# SparkFun_Pi_Wedge_B_Plus_PreAssembled.net
KiCad netlist of a schematic drawn in EAGLE
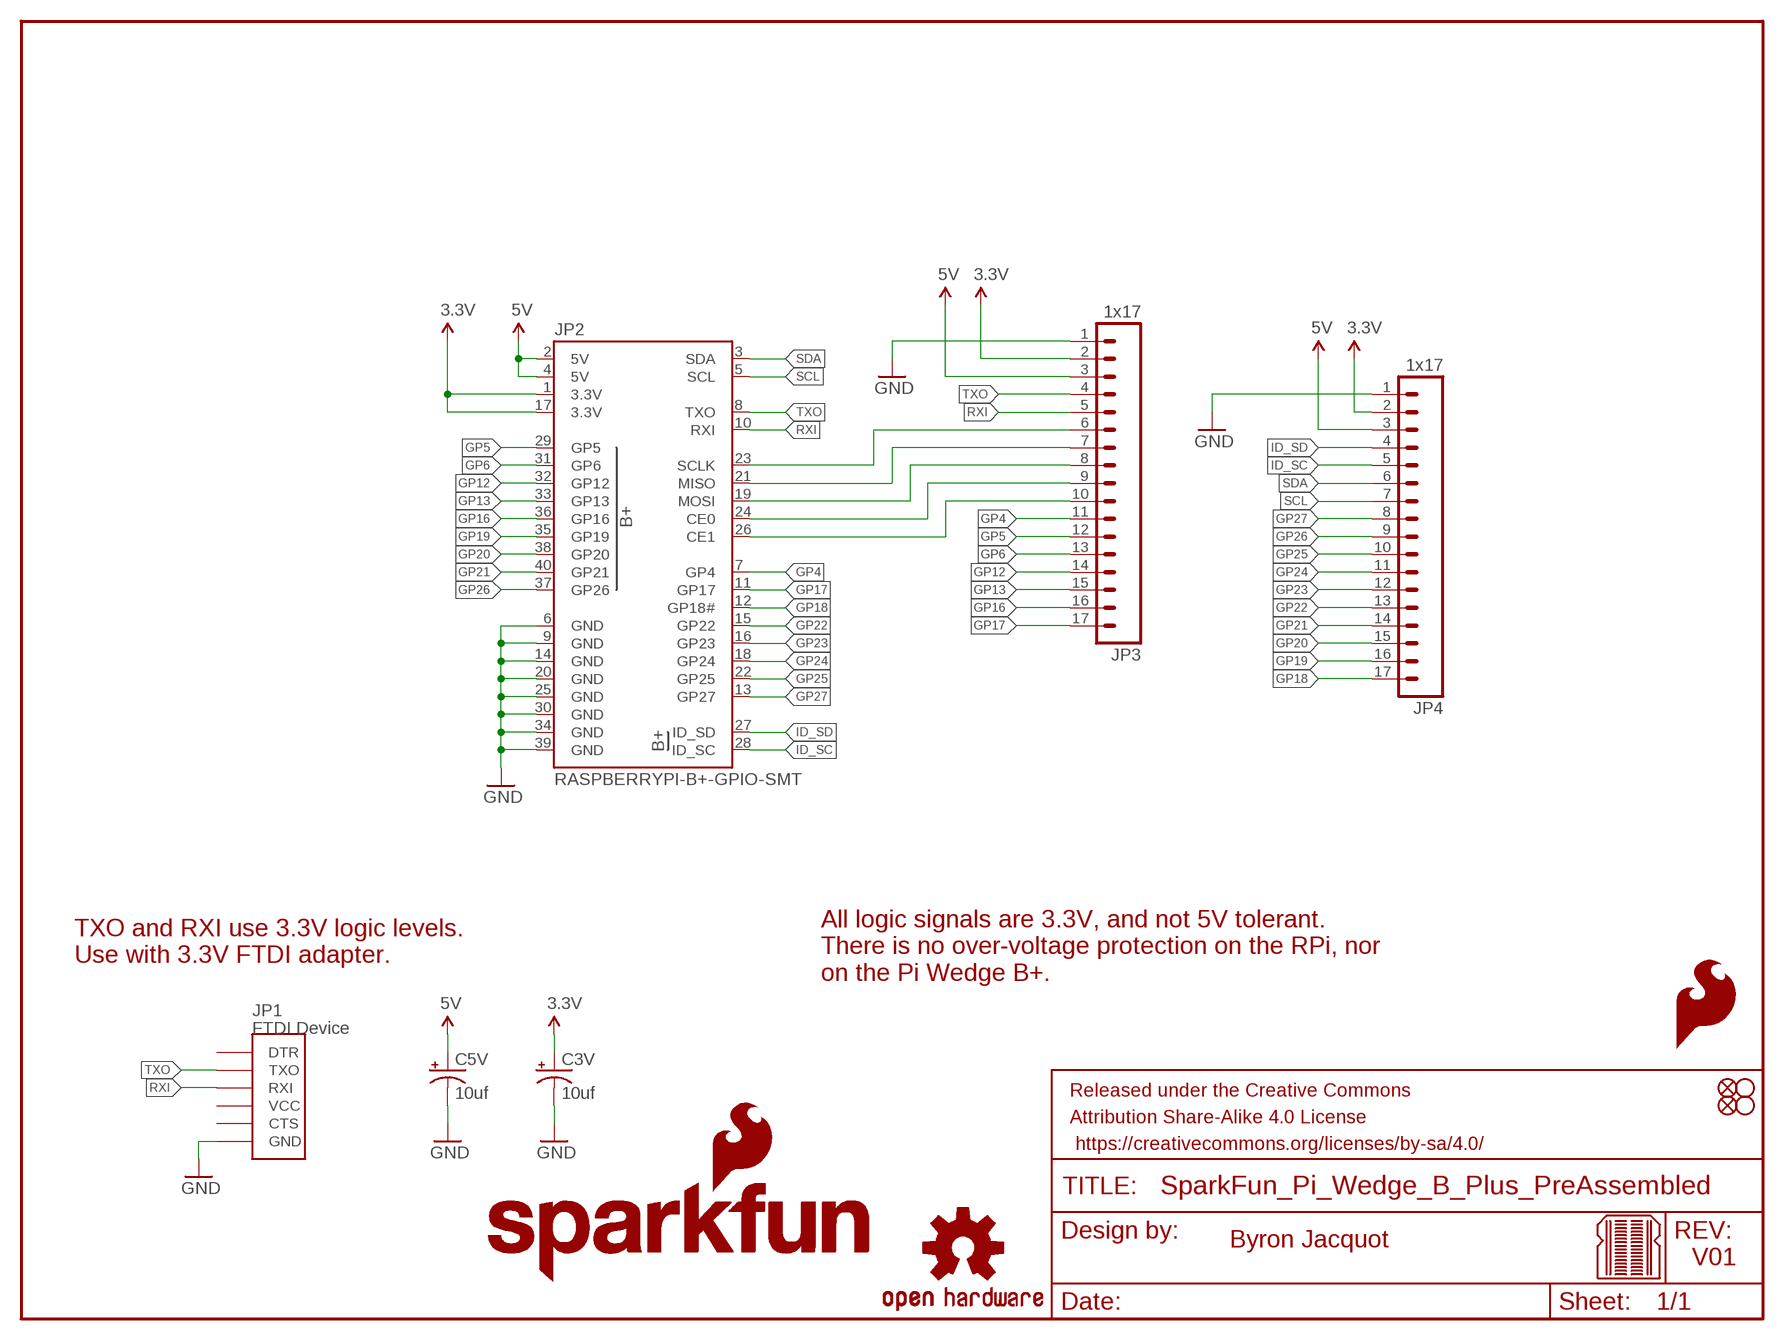
[diagram p0: schematic, sheet 1]

(export (version "E")
  (design (tool "Eeschema 10.0.6"))
  (components
    (comp (ref "C3V")
      (value "10uf")
      (footprint "eagle-import:PANASONIC_D")
      (libsource (lib "eagle-import") (part "47UF-50V-20%(ELECT)"))
    )
    (comp (ref "C5V")
      (value "10uf")
      (footprint "eagle-import:PANASONIC_D")
      (libsource (lib "eagle-import") (part "47UF-50V-20%(ELECT)"))
    )
    (comp (ref "FID1")
      (value "FIDUCIALUFIDUCIAL")
      (footprint "eagle-import:MICRO-FIDUCIAL")
      (libsource (lib "eagle-import") (part "FIDUCIALUFIDUCIAL"))
    )
    (comp (ref "FID2")
      (value "FIDUCIALUFIDUCIAL")
      (footprint "eagle-import:MICRO-FIDUCIAL")
      (libsource (lib "eagle-import") (part "FIDUCIALUFIDUCIAL"))
    )
    (comp (ref "FRAME2")
      (value "FRAME-LETTER")
      (footprint "eagle-import:CREATIVE_COMMONS")
      (libsource (lib "eagle-import") (part "FRAME-LETTER"))
    )
    (comp (ref "JP1")
      (value "FTDI Device")
      (footprint "eagle-import:FTDI_DEVICE_RA_SMT")
      (libsource (lib "eagle-import") (part "FTDI_DEVICERA_SMT"))
    )
    (comp (ref "JP2")
      (value "RASPBERRYPI-B+-GPIO-SMT")
      (footprint "eagle-import:2X20-SHROUDED-SMT")
      (libsource (lib "eagle-import") (part "RASPBERRYPI-B+-GPIO-SMT"))
    )
    (comp (ref "JP3")
      (value "1x17")
      (footprint "eagle-import:1X17_NO_SILK_KIT")
      (libsource (lib "eagle-import") (part "M17KIT"))
    )
    (comp (ref "JP4")
      (value "1x17")
      (footprint "eagle-import:1X17_NO_SILK_KIT")
      (libsource (lib "eagle-import") (part "M17KIT"))
    )
    (comp (ref "LOGO1")
      (value "SFE_LOGO_NAME.2_INCH")
      (footprint "eagle-import:SFE_LOGO_NAME_.2")
      (libsource (lib "eagle-import") (part "SFE_LOGO_NAME.2_INCH"))
    )
    (comp (ref "LOGO2")
      (value "SFE_LOGO_NAME_FLAME.2_INCH")
      (footprint "eagle-import:SFE_LOGO_NAME_FLAME_.2")
      (libsource (lib "eagle-import") (part "SFE_LOGO_NAME_FLAME.2_INCH"))
    )
    (comp (ref "LOGO3")
      (value "SFE_LOGO_FLAME.1_INCH")
      (footprint "eagle-import:SFE_LOGO_FLAME_.1")
      (libsource (lib "eagle-import") (part "SFE_LOGO_FLAME.1_INCH"))
    )
    (comp (ref "LOGO4")
      (value "SFE_LOGO_FLAME.1_INCH")
      (footprint "eagle-import:SFE_LOGO_FLAME_.1")
      (libsource (lib "eagle-import") (part "SFE_LOGO_FLAME.1_INCH"))
    )
    (comp (ref "LOGO5")
      (value "OSHW-LOGOS")
      (footprint "eagle-import:OSHW-LOGO-S")
      (libsource (lib "eagle-import") (part "OSHW-LOGOS"))
    )
    (comp (ref "STANDOFF1")
      (value "STAND-OFF")
      (footprint "eagle-import:STAND-OFF")
      (libsource (lib "eagle-import") (part "STAND-OFF"))
    )
    (comp (ref "STANDOFF2")
      (value "STAND-OFF")
      (footprint "eagle-import:STAND-OFF")
      (libsource (lib "eagle-import") (part "STAND-OFF"))
    )
    (comp (ref "U$2")
      (value "BREADBOARD_PATTERN")
      (footprint "eagle-import:BREADBOARD_SPACING")
      (libsource (lib "eagle-import") (part "BREADBOARD_PATTERN"))
    )
  )
  (nets
    (net (code "1") (name "3.3V") (class "Default")
      (node (ref "C3V") (pin "+") (pinfunction "+_+") (pintype "passive"))
      (node (ref "JP2") (pin "1") (pinfunction "3.3V_1") (pintype "power_in"))
      (node (ref "JP2") (pin "17") (pinfunction "3.3V_17") (pintype "power_in"))
      (node (ref "JP3") (pin "2") (pinfunction "2_2") (pintype "passive"))
      (node (ref "JP4") (pin "2") (pinfunction "2_2") (pintype "passive"))
    )
    (net (code "2") (name "5V") (class "Default")
      (node (ref "C5V") (pin "+") (pinfunction "+_+") (pintype "passive"))
      (node (ref "JP2") (pin "2") (pinfunction "5V_2") (pintype "power_in"))
      (node (ref "JP2") (pin "4") (pinfunction "5V_4") (pintype "power_in"))
      (node (ref "JP3") (pin "3") (pinfunction "3_3") (pintype "passive"))
      (node (ref "JP4") (pin "3") (pinfunction "3_3") (pintype "passive"))
    )
    (net (code "3") (name "GND") (class "Default")
      (node (ref "C3V") (pin "-") (pinfunction "-_-") (pintype "passive"))
      (node (ref "C5V") (pin "-") (pinfunction "-_-") (pintype "passive"))
      (node (ref "JP1") (pin "6") (pinfunction "GND_6") (pintype "bidirectional"))
      (node (ref "JP2") (pin "14") (pinfunction "GND_14") (pintype "power_in"))
      (node (ref "JP2") (pin "20") (pinfunction "GND_20") (pintype "power_in"))
      (node (ref "JP2") (pin "25") (pinfunction "GND_25") (pintype "power_in"))
      (node (ref "JP2") (pin "30") (pinfunction "GND_30") (pintype "power_in"))
      (node (ref "JP2") (pin "34") (pinfunction "GND_34") (pintype "power_in"))
      (node (ref "JP2") (pin "39") (pinfunction "GND_39") (pintype "power_in"))
      (node (ref "JP2") (pin "6") (pinfunction "GND_6") (pintype "power_in"))
      (node (ref "JP2") (pin "9") (pinfunction "GND_9") (pintype "power_in"))
      (node (ref "JP3") (pin "1") (pinfunction "1_1") (pintype "passive"))
      (node (ref "JP4") (pin "1") (pinfunction "1_1") (pintype "passive"))
    )
    (net (code "4") (name "GP4") (class "Default")
      (node (ref "JP2") (pin "7") (pinfunction "GP4_7") (pintype "bidirectional"))
      (node (ref "JP3") (pin "11") (pinfunction "11_11") (pintype "passive"))
    )
    (net (code "5") (name "GP5") (class "Default")
      (node (ref "JP2") (pin "29") (pinfunction "GP5_29") (pintype "bidirectional"))
      (node (ref "JP3") (pin "12") (pinfunction "12_12") (pintype "passive"))
    )
    (net (code "6") (name "GP6") (class "Default")
      (node (ref "JP2") (pin "31") (pinfunction "GP6_31") (pintype "bidirectional"))
      (node (ref "JP3") (pin "13") (pinfunction "13_13") (pintype "passive"))
    )
    (net (code "7") (name "GP12") (class "Default")
      (node (ref "JP2") (pin "32") (pinfunction "GP12_32") (pintype "bidirectional"))
      (node (ref "JP3") (pin "14") (pinfunction "14_14") (pintype "passive"))
    )
    (net (code "8") (name "GP13") (class "Default")
      (node (ref "JP2") (pin "33") (pinfunction "GP13_33") (pintype "bidirectional"))
      (node (ref "JP3") (pin "15") (pinfunction "15_15") (pintype "passive"))
    )
    (net (code "9") (name "GP16") (class "Default")
      (node (ref "JP2") (pin "36") (pinfunction "GP16_36") (pintype "bidirectional"))
      (node (ref "JP3") (pin "16") (pinfunction "16_16") (pintype "passive"))
    )
    (net (code "10") (name "GP17") (class "Default")
      (node (ref "JP2") (pin "11") (pinfunction "GP17_11") (pintype "bidirectional"))
      (node (ref "JP3") (pin "17") (pinfunction "17_17") (pintype "passive"))
    )
    (net (code "11") (name "GP18") (class "Default")
      (node (ref "JP2") (pin "12") (pinfunction "GP18#_12") (pintype "bidirectional"))
      (node (ref "JP4") (pin "17") (pinfunction "17_17") (pintype "passive"))
    )
    (net (code "12") (name "GP19") (class "Default")
      (node (ref "JP2") (pin "35") (pinfunction "GP19_35") (pintype "bidirectional"))
      (node (ref "JP4") (pin "16") (pinfunction "16_16") (pintype "passive"))
    )
    (net (code "13") (name "GP20") (class "Default")
      (node (ref "JP2") (pin "38") (pinfunction "GP20_38") (pintype "bidirectional"))
      (node (ref "JP4") (pin "15") (pinfunction "15_15") (pintype "passive"))
    )
    (net (code "14") (name "GP21") (class "Default")
      (node (ref "JP2") (pin "40") (pinfunction "GP21_40") (pintype "bidirectional"))
      (node (ref "JP4") (pin "14") (pinfunction "14_14") (pintype "passive"))
    )
    (net (code "15") (name "GP22") (class "Default")
      (node (ref "JP2") (pin "15") (pinfunction "GP22_15") (pintype "bidirectional"))
      (node (ref "JP4") (pin "13") (pinfunction "13_13") (pintype "passive"))
    )
    (net (code "16") (name "GP23") (class "Default")
      (node (ref "JP2") (pin "16") (pinfunction "GP23_16") (pintype "bidirectional"))
      (node (ref "JP4") (pin "12") (pinfunction "12_12") (pintype "passive"))
    )
    (net (code "17") (name "GP24") (class "Default")
      (node (ref "JP2") (pin "18") (pinfunction "GP24_18") (pintype "bidirectional"))
      (node (ref "JP4") (pin "11") (pinfunction "11_11") (pintype "passive"))
    )
    (net (code "18") (name "GP25") (class "Default")
      (node (ref "JP2") (pin "22") (pinfunction "GP25_22") (pintype "bidirectional"))
      (node (ref "JP4") (pin "10") (pinfunction "10_10") (pintype "passive"))
    )
    (net (code "19") (name "GP26") (class "Default")
      (node (ref "JP2") (pin "37") (pinfunction "GP26_37") (pintype "bidirectional"))
      (node (ref "JP4") (pin "9") (pinfunction "9_9") (pintype "passive"))
    )
    (net (code "20") (name "GP27") (class "Default")
      (node (ref "JP2") (pin "13") (pinfunction "GP27_13") (pintype "bidirectional"))
      (node (ref "JP4") (pin "8") (pinfunction "8_8") (pintype "passive"))
    )
    (net (code "21") (name "ID_SC") (class "Default")
      (node (ref "JP2") (pin "28") (pinfunction "ID_SC_28") (pintype "bidirectional"))
      (node (ref "JP4") (pin "5") (pinfunction "5_5") (pintype "passive"))
    )
    (net (code "22") (name "ID_SD") (class "Default")
      (node (ref "JP2") (pin "27") (pinfunction "ID_SD_27") (pintype "bidirectional"))
      (node (ref "JP4") (pin "4") (pinfunction "4_4") (pintype "passive"))
    )
    (net (code "23") (name "Net-(JP2-CE0)") (class "Default")
      (node (ref "JP2") (pin "24") (pinfunction "CE0_24") (pintype "output"))
      (node (ref "JP3") (pin "9") (pinfunction "9_9") (pintype "passive"))
    )
    (net (code "24") (name "Net-(JP2-CE1)") (class "Default")
      (node (ref "JP2") (pin "26") (pinfunction "CE1_26") (pintype "output"))
      (node (ref "JP3") (pin "10") (pinfunction "10_10") (pintype "passive"))
    )
    (net (code "25") (name "Net-(JP2-MISO)") (class "Default")
      (node (ref "JP2") (pin "21") (pinfunction "MISO_21") (pintype "input"))
      (node (ref "JP3") (pin "7") (pinfunction "7_7") (pintype "passive"))
    )
    (net (code "26") (name "Net-(JP2-MOSI)") (class "Default")
      (node (ref "JP2") (pin "19") (pinfunction "MOSI_19") (pintype "output"))
      (node (ref "JP3") (pin "8") (pinfunction "8_8") (pintype "passive"))
    )
    (net (code "27") (name "Net-(JP2-SCLK)") (class "Default")
      (node (ref "JP2") (pin "23") (pinfunction "SCLK_23") (pintype "output"))
      (node (ref "JP3") (pin "6") (pinfunction "6_6") (pintype "passive"))
    )
    (net (code "28") (name "RXI") (class "Default")
      (node (ref "JP1") (pin "3") (pinfunction "RXI_3") (pintype "bidirectional"))
      (node (ref "JP2") (pin "10") (pinfunction "RXI_10") (pintype "input"))
      (node (ref "JP3") (pin "5") (pinfunction "5_5") (pintype "passive"))
    )
    (net (code "29") (name "SCL") (class "Default")
      (node (ref "JP2") (pin "5") (pinfunction "SCL_5") (pintype "bidirectional"))
      (node (ref "JP4") (pin "7") (pinfunction "7_7") (pintype "passive"))
    )
    (net (code "30") (name "SDA") (class "Default")
      (node (ref "JP2") (pin "3") (pinfunction "SDA_3") (pintype "bidirectional"))
      (node (ref "JP4") (pin "6") (pinfunction "6_6") (pintype "passive"))
    )
    (net (code "31") (name "TXO") (class "Default")
      (node (ref "JP1") (pin "2") (pinfunction "TXO_2") (pintype "bidirectional"))
      (node (ref "JP2") (pin "8") (pinfunction "TXO_8") (pintype "output"))
      (node (ref "JP3") (pin "4") (pinfunction "4_4") (pintype "passive"))
    )
    (net (code "32") (name "unconnected-(JP1-CTS-Pad5)") (class "Default")
      (node (ref "JP1") (pin "5") (pinfunction "CTS_5") (pintype "bidirectional"))
    )
    (net (code "33") (name "unconnected-(JP1-DTR-Pad1)") (class "Default")
      (node (ref "JP1") (pin "1") (pinfunction "DTR_1") (pintype "bidirectional"))
    )
    (net (code "34") (name "unconnected-(JP1-VCC-Pad4)") (class "Default")
      (node (ref "JP1") (pin "4") (pinfunction "VCC_4") (pintype "bidirectional"))
    )
  )
)
